# untitled.net
KiCad netlist of a schematic drawn in EAGLE
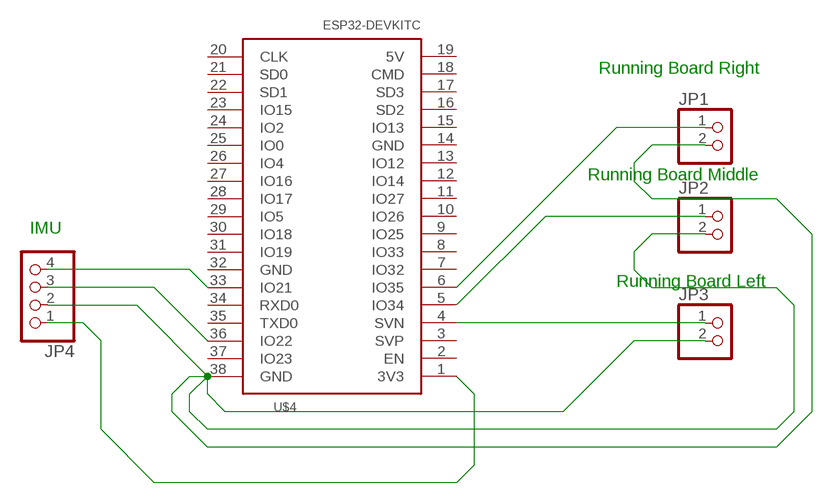
[diagram p0: schematic, sheet 1]

(export (version "E")
  (design (tool "Eeschema 10.0.6"))
  (components
    (comp (ref "JP1")
      (value "PINHD-1X2")
      (footprint "eagle-import:1X02")
      (libsource (lib "eagle-import") (part "PINHD-1X2"))
    )
    (comp (ref "JP2")
      (value "PINHD-1X2")
      (footprint "eagle-import:1X02")
      (libsource (lib "eagle-import") (part "PINHD-1X2"))
    )
    (comp (ref "JP3")
      (value "PINHD-1X2")
      (footprint "eagle-import:1X02")
      (libsource (lib "eagle-import") (part "PINHD-1X2"))
    )
    (comp (ref "JP4")
      (value "PINHD-1X4")
      (footprint "eagle-import:1X04")
      (libsource (lib "eagle-import") (part "PINHD-1X4"))
    )
    (comp (ref "U$4")
      (value "ESP32DEVKITC")
      (footprint "eagle-import:ESP32-DEVKITC")
      (libsource (lib "eagle-import") (part "ESP32DEVKITC"))
    )
  )
  (nets
    (net (code "1") (name "Net-(JP1-Pad2)") (class "Default")
      (node (ref "JP1") (pin "2") (pinfunction "2_2") (pintype "passive"))
      (node (ref "JP2") (pin "2") (pinfunction "2_2") (pintype "passive"))
      (node (ref "JP3") (pin "2") (pinfunction "2_2") (pintype "passive"))
      (node (ref "JP4") (pin "2") (pinfunction "2_2") (pintype "passive"))
      (node (ref "U$4") (pin "38") (pinfunction "GND_38") (pintype "bidirectional"))
    )
    (net (code "2") (name "Net-(U$4-3V3)") (class "Default")
      (node (ref "JP4") (pin "1") (pinfunction "1_1") (pintype "passive"))
      (node (ref "U$4") (pin "1") (pinfunction "3V3_1") (pintype "bidirectional"))
    )
    (net (code "3") (name "Net-(U$4-IO21)") (class "Default")
      (node (ref "JP4") (pin "4") (pinfunction "4_4") (pintype "passive"))
      (node (ref "U$4") (pin "33") (pinfunction "IO21_33") (pintype "bidirectional"))
    )
    (net (code "4") (name "Net-(U$4-IO22)") (class "Default")
      (node (ref "JP4") (pin "3") (pinfunction "3_3") (pintype "passive"))
      (node (ref "U$4") (pin "36") (pinfunction "IO22_36") (pintype "bidirectional"))
    )
    (net (code "5") (name "Net-(U$4-IO34)") (class "Default")
      (node (ref "JP2") (pin "1") (pinfunction "1_1") (pintype "passive"))
      (node (ref "U$4") (pin "5") (pinfunction "IO34_5") (pintype "bidirectional"))
    )
    (net (code "6") (name "Net-(U$4-IO35)") (class "Default")
      (node (ref "JP1") (pin "1") (pinfunction "1_1") (pintype "passive"))
      (node (ref "U$4") (pin "6") (pinfunction "IO35_6") (pintype "bidirectional"))
    )
    (net (code "7") (name "Net-(U$4-SVN)") (class "Default")
      (node (ref "JP3") (pin "1") (pinfunction "1_1") (pintype "passive"))
      (node (ref "U$4") (pin "4") (pinfunction "SVN_4") (pintype "bidirectional"))
    )
    (net (code "8") (name "unconnected-(U$4-5V-Pad19)") (class "Default")
      (node (ref "U$4") (pin "19") (pinfunction "5V_19") (pintype "bidirectional"))
    )
    (net (code "9") (name "unconnected-(U$4-CLK-Pad20)") (class "Default")
      (node (ref "U$4") (pin "20") (pinfunction "CLK_20") (pintype "bidirectional"))
    )
    (net (code "10") (name "unconnected-(U$4-CMD-Pad18)") (class "Default")
      (node (ref "U$4") (pin "18") (pinfunction "CMD_18") (pintype "bidirectional"))
    )
    (net (code "11") (name "unconnected-(U$4-EN-Pad2)") (class "Default")
      (node (ref "U$4") (pin "2") (pinfunction "EN_2") (pintype "bidirectional"))
    )
    (net (code "12") (name "unconnected-(U$4-GND-Pad14)") (class "Default")
      (node (ref "U$4") (pin "14") (pinfunction "GND_14") (pintype "bidirectional"))
    )
    (net (code "13") (name "unconnected-(U$4-GND-Pad32)") (class "Default")
      (node (ref "U$4") (pin "32") (pinfunction "GND_32") (pintype "bidirectional"))
    )
    (net (code "14") (name "unconnected-(U$4-IO0-Pad25)") (class "Default")
      (node (ref "U$4") (pin "25") (pinfunction "IO0_25") (pintype "bidirectional"))
    )
    (net (code "15") (name "unconnected-(U$4-IO2-Pad24)") (class "Default")
      (node (ref "U$4") (pin "24") (pinfunction "IO2_24") (pintype "bidirectional"))
    )
    (net (code "16") (name "unconnected-(U$4-IO4-Pad26)") (class "Default")
      (node (ref "U$4") (pin "26") (pinfunction "IO4_26") (pintype "bidirectional"))
    )
    (net (code "17") (name "unconnected-(U$4-IO5-Pad29)") (class "Default")
      (node (ref "U$4") (pin "29") (pinfunction "IO5_29") (pintype "bidirectional"))
    )
    (net (code "18") (name "unconnected-(U$4-IO12-Pad13)") (class "Default")
      (node (ref "U$4") (pin "13") (pinfunction "IO12_13") (pintype "bidirectional"))
    )
    (net (code "19") (name "unconnected-(U$4-IO13-Pad15)") (class "Default")
      (node (ref "U$4") (pin "15") (pinfunction "IO13_15") (pintype "bidirectional"))
    )
    (net (code "20") (name "unconnected-(U$4-IO14-Pad12)") (class "Default")
      (node (ref "U$4") (pin "12") (pinfunction "IO14_12") (pintype "bidirectional"))
    )
    (net (code "21") (name "unconnected-(U$4-IO15-Pad23)") (class "Default")
      (node (ref "U$4") (pin "23") (pinfunction "IO15_23") (pintype "bidirectional"))
    )
    (net (code "22") (name "unconnected-(U$4-IO16-Pad27)") (class "Default")
      (node (ref "U$4") (pin "27") (pinfunction "IO16_27") (pintype "bidirectional"))
    )
    (net (code "23") (name "unconnected-(U$4-IO17-Pad28)") (class "Default")
      (node (ref "U$4") (pin "28") (pinfunction "IO17_28") (pintype "bidirectional"))
    )
    (net (code "24") (name "unconnected-(U$4-IO18-Pad30)") (class "Default")
      (node (ref "U$4") (pin "30") (pinfunction "IO18_30") (pintype "bidirectional"))
    )
    (net (code "25") (name "unconnected-(U$4-IO19-Pad31)") (class "Default")
      (node (ref "U$4") (pin "31") (pinfunction "IO19_31") (pintype "bidirectional"))
    )
    (net (code "26") (name "unconnected-(U$4-IO23-Pad37)") (class "Default")
      (node (ref "U$4") (pin "37") (pinfunction "IO23_37") (pintype "bidirectional"))
    )
    (net (code "27") (name "unconnected-(U$4-IO25-Pad9)") (class "Default")
      (node (ref "U$4") (pin "9") (pinfunction "IO25_9") (pintype "bidirectional"))
    )
    (net (code "28") (name "unconnected-(U$4-IO26-Pad10)") (class "Default")
      (node (ref "U$4") (pin "10") (pinfunction "IO26_10") (pintype "bidirectional"))
    )
    (net (code "29") (name "unconnected-(U$4-IO27-Pad11)") (class "Default")
      (node (ref "U$4") (pin "11") (pinfunction "IO27_11") (pintype "bidirectional"))
    )
    (net (code "30") (name "unconnected-(U$4-IO32-Pad7)") (class "Default")
      (node (ref "U$4") (pin "7") (pinfunction "IO32_7") (pintype "bidirectional"))
    )
    (net (code "31") (name "unconnected-(U$4-IO33-Pad8)") (class "Default")
      (node (ref "U$4") (pin "8") (pinfunction "IO33_8") (pintype "bidirectional"))
    )
    (net (code "32") (name "unconnected-(U$4-RXD0-Pad34)") (class "Default")
      (node (ref "U$4") (pin "34") (pinfunction "RXD0_34") (pintype "bidirectional"))
    )
    (net (code "33") (name "unconnected-(U$4-SD0-Pad21)") (class "Default")
      (node (ref "U$4") (pin "21") (pinfunction "SD0_21") (pintype "bidirectional"))
    )
    (net (code "34") (name "unconnected-(U$4-SD1-Pad22)") (class "Default")
      (node (ref "U$4") (pin "22") (pinfunction "SD1_22") (pintype "bidirectional"))
    )
    (net (code "35") (name "unconnected-(U$4-SD2-Pad16)") (class "Default")
      (node (ref "U$4") (pin "16") (pinfunction "SD2_16") (pintype "bidirectional"))
    )
    (net (code "36") (name "unconnected-(U$4-SD3-Pad17)") (class "Default")
      (node (ref "U$4") (pin "17") (pinfunction "SD3_17") (pintype "bidirectional"))
    )
    (net (code "37") (name "unconnected-(U$4-SVP-Pad3)") (class "Default")
      (node (ref "U$4") (pin "3") (pinfunction "SVP_3") (pintype "bidirectional"))
    )
    (net (code "38") (name "unconnected-(U$4-TXD0-Pad35)") (class "Default")
      (node (ref "U$4") (pin "35") (pinfunction "TXD0_35") (pintype "bidirectional"))
    )
  )
)
